# 28Pins_Project_V1I1.net
KiCad netlist of a schematic drawn in Altium Designer
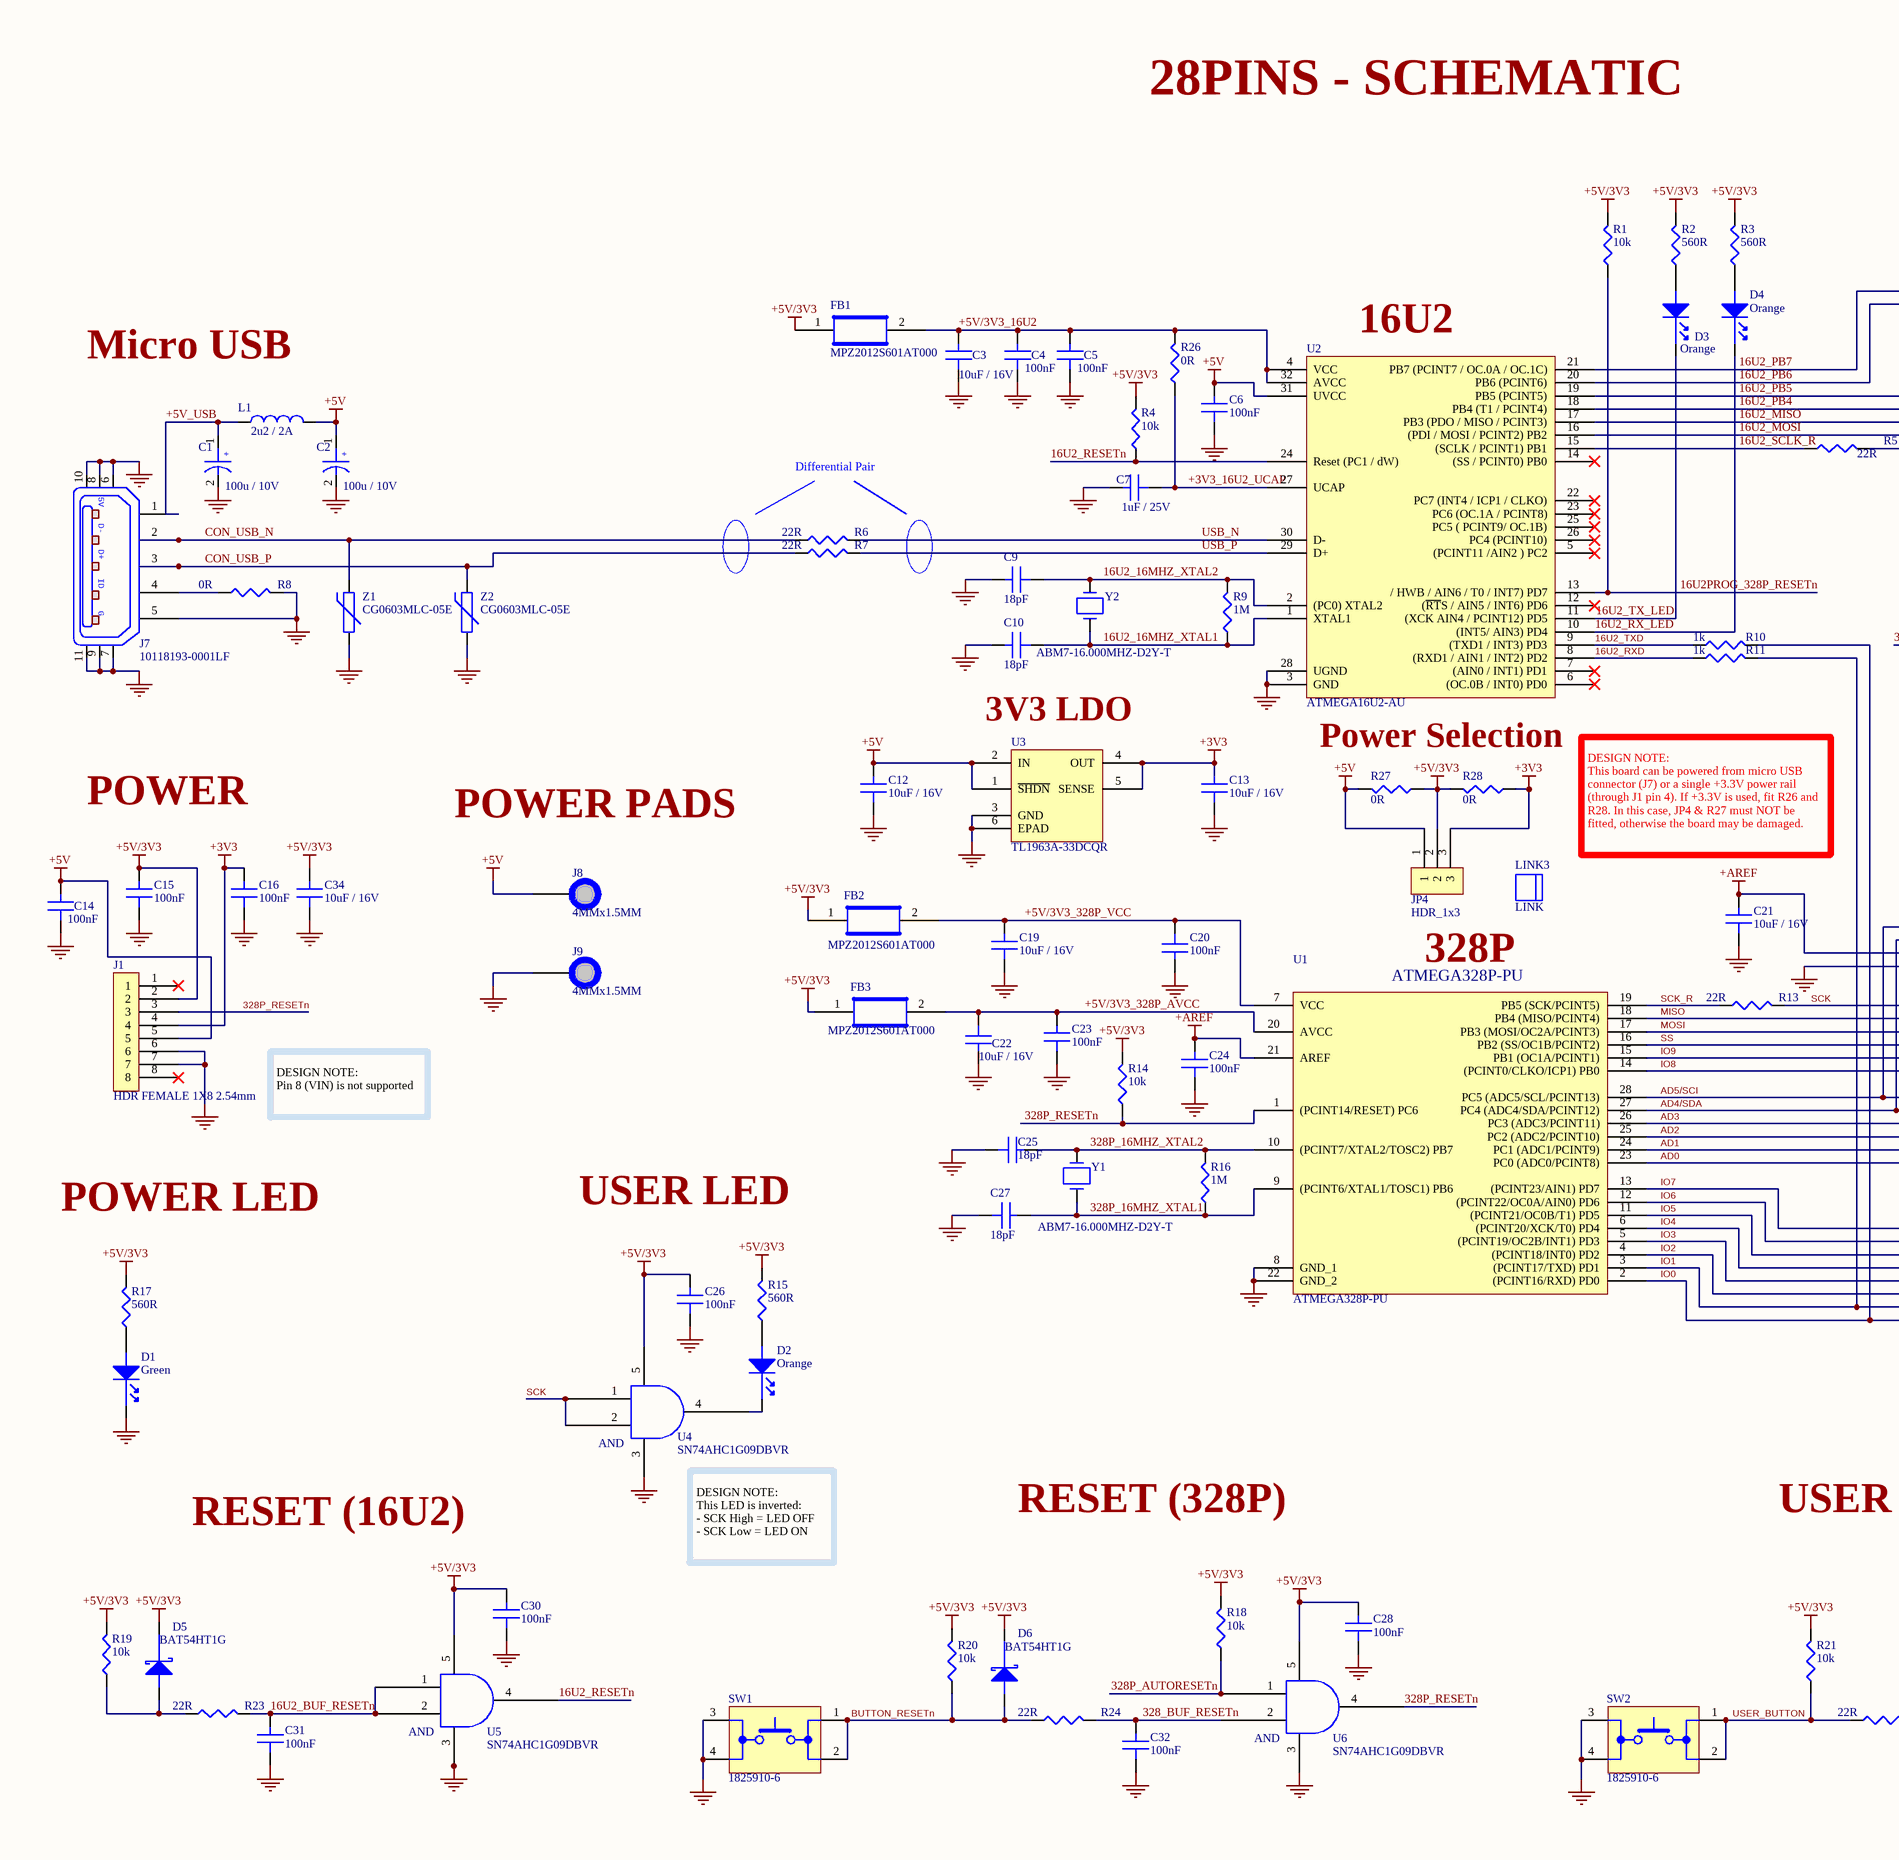
[diagram p0: 28Pins_Project_V1I1.SchDoc, left]
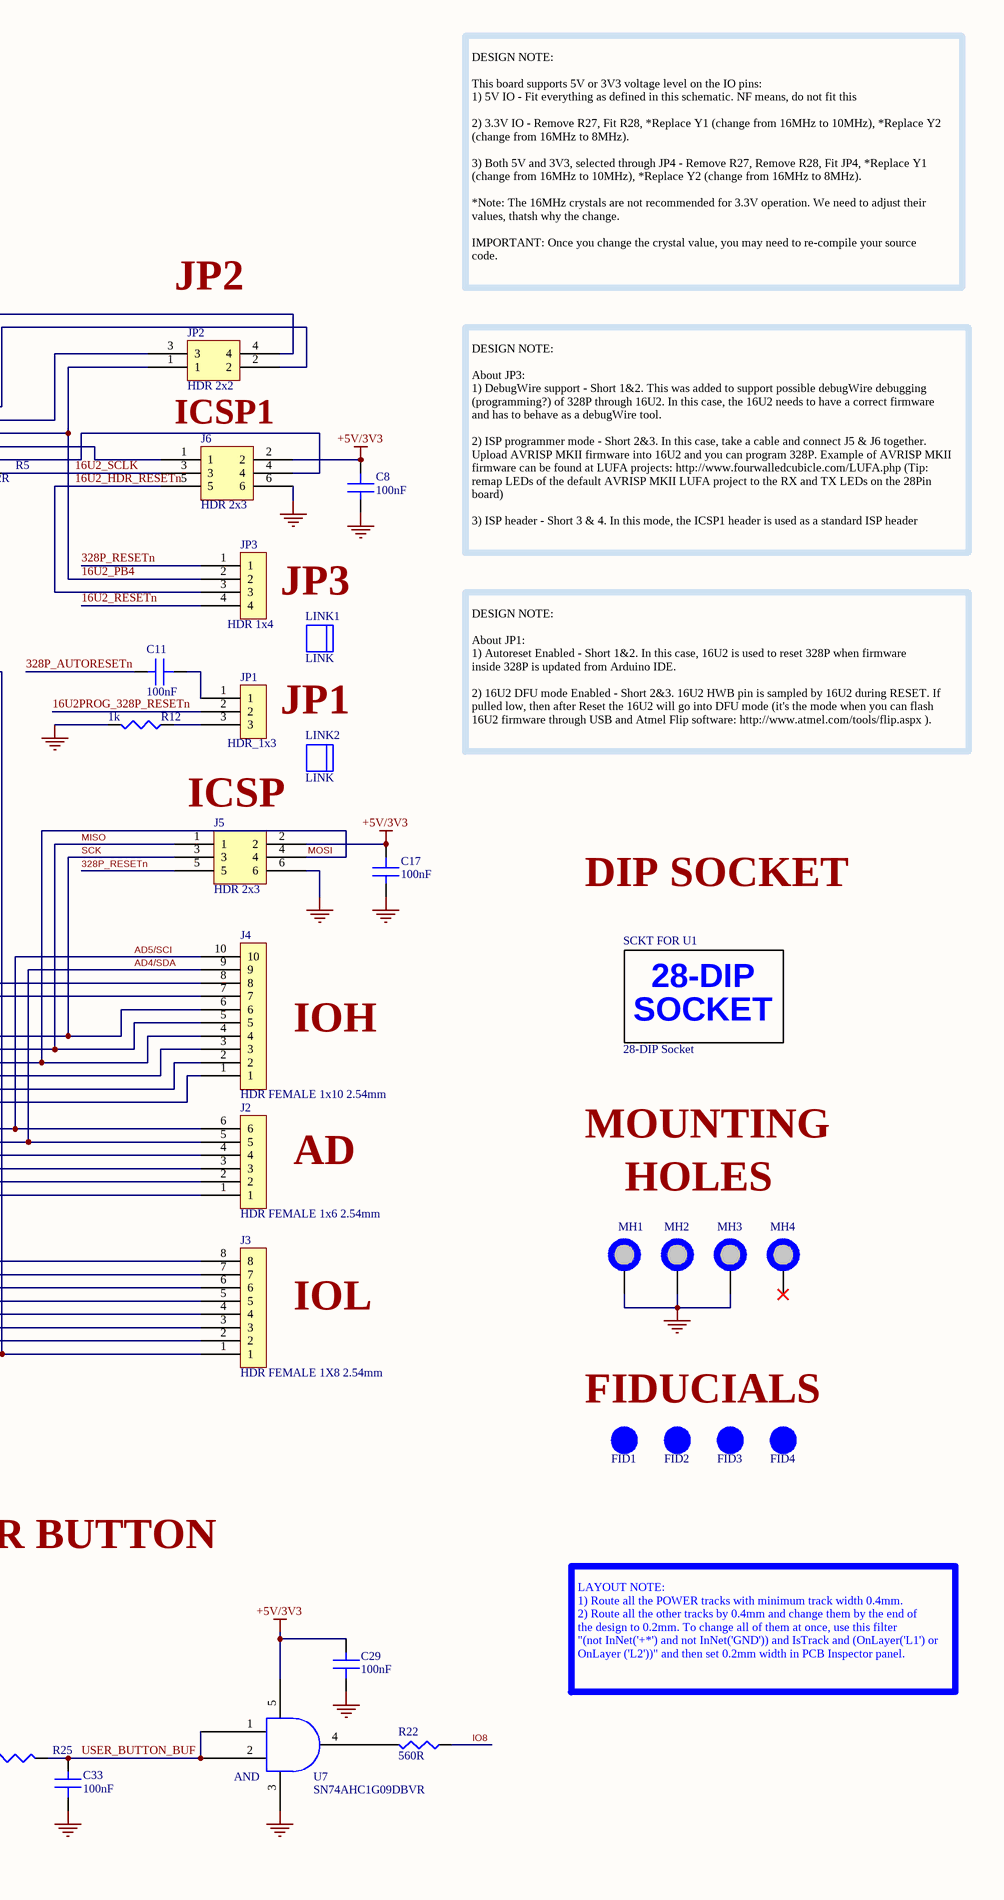
[diagram p1: 28Pins_Project_V1I1.SchDoc, right]

(export (version "E")
  (design (tool "Eeschema 10.0.6"))
  (components
    (comp (ref "C1")
      (value "100u / 10V")
      (footprint "C_ALU_C_SIZE")
      (description "CAP ALUM 100UF 20% 10V SMD")
      (fields
        (field (name "MANUFACTURER") "Panasonic")
        (field (name "MANUFACTURER PART NUMBER") "EEE-1AA101WR")
      )
      (libsource (lib "28Pins_Project_V1I1") (part "Tantal Capacitor"))
    )
    (comp (ref "C2")
      (value "100u / 10V")
      (footprint "C_ALU_C_SIZE")
      (description "CAP ALUM 100UF 20% 10V SMD")
      (fields
        (field (name "MANUFACTURER") "Panasonic")
        (field (name "MANUFACTURER PART NUMBER") "EEE-1AA101WR")
      )
      (libsource (lib "28Pins_Project_V1I1") (part "Tantal Capacitor"))
    )
    (comp (ref "C3")
      (value "10uF / 16V")
      (footprint "Capacitor 0805")
      (fields
        (field (name "MANUFACTURER") "TDK")
        (field (name "MANUFACTURER PART NUMBER") "C2012X5R1C106M125AC")
        (field (name "TOLERANCE") "20%")
      )
      (libsource (lib "28Pins_Project_V1I1") (part "C2012X5R1C106M125AC"))
    )
    (comp (ref "C4")
      (value "100nF")
      (footprint "Capacitor 0805")
      (description "100 nF Capacitor")
      (libsource (lib "28Pins_Project_V1I1") (part "CAP 0805 100nF"))
    )
    (comp (ref "C5")
      (value "100nF")
      (footprint "Capacitor 0805")
      (description "100 nF Capacitor")
      (libsource (lib "28Pins_Project_V1I1") (part "CAP 0805 100nF"))
    )
    (comp (ref "C6")
      (value "100nF")
      (footprint "Capacitor 0805")
      (description "100 nF Capacitor")
      (libsource (lib "28Pins_Project_V1I1") (part "CAP 0805 100nF"))
    )
    (comp (ref "C7")
      (value "1uF / 25V")
      (footprint "Capacitor 0805")
      (description "CAP CER 1UF 25V X5R 0805")
      (fields
        (field (name "MANUFACTURER") "TDK")
        (field (name "MANUFACTURER PART NUMBER") "C2012X5R1E105K125AA")
      )
      (libsource (lib "28Pins_Project_V1I1") (part "C2012X5R1E105K125AA"))
    )
    (comp (ref "C8")
      (value "100nF")
      (footprint "Capacitor 0805")
      (description "100 nF Capacitor")
      (libsource (lib "28Pins_Project_V1I1") (part "CAP 0805 100nF"))
    )
    (comp (ref "C9")
      (value "18pF")
      (footprint "Capacitor 0805")
      (description "Cap Ceramic 18pF 50V C0G 5% SMD 0805 125C Paper T/R")
      (fields
        (field (name "MANUFACTURER") "KEMET")
        (field (name "MANUFACTURER PART NUMBER") "C0805C180J5GACTU")
      )
      (libsource (lib "28Pins_Project_V1I1") (part "C0805C180J5GACTU"))
    )
    (comp (ref "C10")
      (value "18pF")
      (footprint "Capacitor 0805")
      (description "Cap Ceramic 18pF 50V C0G 5% SMD 0805 125C Paper T/R")
      (fields
        (field (name "MANUFACTURER") "KEMET")
        (field (name "MANUFACTURER PART NUMBER") "C0805C180J5GACTU")
      )
      (libsource (lib "28Pins_Project_V1I1") (part "C0805C180J5GACTU"))
    )
    (comp (ref "C11")
      (value "100nF")
      (footprint "Capacitor 0805")
      (description "100 nF Capacitor")
      (libsource (lib "28Pins_Project_V1I1") (part "CAP 0805 100nF"))
    )
    (comp (ref "C12")
      (value "10uF / 16V")
      (footprint "Capacitor 0805")
      (fields
        (field (name "MANUFACTURER") "TDK")
        (field (name "MANUFACTURER PART NUMBER") "C2012X5R1C106M125AC")
        (field (name "TOLERANCE") "20%")
      )
      (libsource (lib "28Pins_Project_V1I1") (part "C2012X5R1C106M125AC"))
    )
    (comp (ref "C13")
      (value "10uF / 16V")
      (footprint "Capacitor 0805")
      (fields
        (field (name "MANUFACTURER") "TDK")
        (field (name "MANUFACTURER PART NUMBER") "C2012X5R1C106M125AC")
        (field (name "TOLERANCE") "20%")
      )
      (libsource (lib "28Pins_Project_V1I1") (part "C2012X5R1C106M125AC"))
    )
    (comp (ref "C14")
      (value "100nF")
      (footprint "Capacitor 0805")
      (description "100 nF Capacitor")
      (libsource (lib "28Pins_Project_V1I1") (part "CAP 0805 100nF"))
    )
    (comp (ref "C15")
      (value "100nF")
      (footprint "Capacitor 0805")
      (description "100 nF Capacitor")
      (libsource (lib "28Pins_Project_V1I1") (part "CAP 0805 100nF"))
    )
    (comp (ref "C16")
      (value "100nF")
      (footprint "Capacitor 0805")
      (description "100 nF Capacitor")
      (libsource (lib "28Pins_Project_V1I1") (part "CAP 0805 100nF"))
    )
    (comp (ref "C17")
      (value "100nF")
      (footprint "Capacitor 0805")
      (description "100 nF Capacitor")
      (libsource (lib "28Pins_Project_V1I1") (part "CAP 0805 100nF"))
    )
    (comp (ref "C19")
      (value "10uF / 16V")
      (footprint "Capacitor 0805")
      (fields
        (field (name "MANUFACTURER") "TDK")
        (field (name "MANUFACTURER PART NUMBER") "C2012X5R1C106M125AC")
        (field (name "TOLERANCE") "20%")
      )
      (libsource (lib "28Pins_Project_V1I1") (part "C2012X5R1C106M125AC"))
    )
    (comp (ref "C20")
      (value "100nF")
      (footprint "Capacitor 0805")
      (description "100 nF Capacitor")
      (libsource (lib "28Pins_Project_V1I1") (part "CAP 0805 100nF"))
    )
    (comp (ref "C21")
      (value "10uF / 16V")
      (footprint "Capacitor 0805")
      (fields
        (field (name "MANUFACTURER") "TDK")
        (field (name "MANUFACTURER PART NUMBER") "C2012X5R1C106M125AC")
        (field (name "TOLERANCE") "20%")
      )
      (libsource (lib "28Pins_Project_V1I1") (part "C2012X5R1C106M125AC"))
    )
    (comp (ref "C22")
      (value "10uF / 16V")
      (footprint "Capacitor 0805")
      (fields
        (field (name "MANUFACTURER") "TDK")
        (field (name "MANUFACTURER PART NUMBER") "C2012X5R1C106M125AC")
        (field (name "TOLERANCE") "20%")
      )
      (libsource (lib "28Pins_Project_V1I1") (part "C2012X5R1C106M125AC"))
    )
    (comp (ref "C23")
      (value "100nF")
      (footprint "Capacitor 0805")
      (description "100 nF Capacitor")
      (libsource (lib "28Pins_Project_V1I1") (part "CAP 0805 100nF"))
    )
    (comp (ref "C24")
      (value "100nF")
      (footprint "Capacitor 0805")
      (description "100 nF Capacitor")
      (libsource (lib "28Pins_Project_V1I1") (part "CAP 0805 100nF"))
    )
    (comp (ref "C25")
      (value "18pF")
      (footprint "Capacitor 0805")
      (description "Cap Ceramic 18pF 50V C0G 5% SMD 0805 125C Paper T/R")
      (fields
        (field (name "MANUFACTURER") "KEMET")
        (field (name "MANUFACTURER PART NUMBER") "C0805C180J5GACTU")
      )
      (libsource (lib "28Pins_Project_V1I1") (part "C0805C180J5GACTU"))
    )
    (comp (ref "C26")
      (value "100nF")
      (footprint "Capacitor 0805")
      (description "100 nF Capacitor")
      (libsource (lib "28Pins_Project_V1I1") (part "CAP 0805 100nF"))
    )
    (comp (ref "C27")
      (value "18pF")
      (footprint "Capacitor 0805")
      (description "Cap Ceramic 18pF 50V C0G 5% SMD 0805 125C Paper T/R")
      (fields
        (field (name "MANUFACTURER") "KEMET")
        (field (name "MANUFACTURER PART NUMBER") "C0805C180J5GACTU")
      )
      (libsource (lib "28Pins_Project_V1I1") (part "C0805C180J5GACTU"))
    )
    (comp (ref "C28")
      (value "100nF")
      (footprint "Capacitor 0805")
      (description "100 nF Capacitor")
      (libsource (lib "28Pins_Project_V1I1") (part "CAP 0805 100nF"))
    )
    (comp (ref "C29")
      (value "100nF")
      (footprint "Capacitor 0805")
      (description "100 nF Capacitor")
      (libsource (lib "28Pins_Project_V1I1") (part "CAP 0805 100nF"))
    )
    (comp (ref "C30")
      (value "100nF")
      (footprint "Capacitor 0805")
      (description "100 nF Capacitor")
      (libsource (lib "28Pins_Project_V1I1") (part "CAP 0805 100nF"))
    )
    (comp (ref "C31")
      (value "100nF")
      (footprint "Capacitor 0805")
      (description "100 nF Capacitor")
      (libsource (lib "28Pins_Project_V1I1") (part "CAP 0805 100nF"))
    )
    (comp (ref "C32")
      (value "100nF")
      (footprint "Capacitor 0805")
      (description "100 nF Capacitor")
      (libsource (lib "28Pins_Project_V1I1") (part "CAP 0805 100nF"))
    )
    (comp (ref "C33")
      (value "100nF")
      (footprint "Capacitor 0805")
      (description "100 nF Capacitor")
      (libsource (lib "28Pins_Project_V1I1") (part "CAP 0805 100nF"))
    )
    (comp (ref "C34")
      (value "10uF / 16V")
      (footprint "Capacitor 0805")
      (fields
        (field (name "MANUFACTURER") "TDK")
        (field (name "MANUFACTURER PART NUMBER") "C2012X5R1C106M125AC")
        (field (name "TOLERANCE") "20%")
      )
      (libsource (lib "28Pins_Project_V1I1") (part "C2012X5R1C106M125AC"))
    )
    (comp (ref "D1")
      (value "Green")
      (footprint "LED_0603")
      (description "LED GREEN DIFFUSED 0603 SMD")
      (fields
        (field (name "MANUFACTURER") "Osram Opto")
        (field (name "MANUFACTURER PART NUMBER") "LGL29K-G2J1-24-Z")
      )
      (libsource (lib "28Pins_Project_V1I1") (part "LGL29K-G2J1-24-Z"))
    )
    (comp (ref "D2")
      (value "Orange")
      (footprint "LED_0603")
      (description "LED Orange Diffused 0603 SMD")
      (fields
        (field (name "MANUFACTURER") "Osram Opto")
        (field (name "MANUFACTURER PART NUMBER") "LOL29K-H2K1-24-Z")
      )
      (libsource (lib "28Pins_Project_V1I1") (part "LOL29K-H2K1-24-Z"))
    )
    (comp (ref "D3")
      (value "Orange")
      (footprint "LED_0603")
      (description "LED Orange Diffused 0603 SMD")
      (fields
        (field (name "MANUFACTURER") "Osram Opto")
        (field (name "MANUFACTURER PART NUMBER") "LOL29K-H2K1-24-Z")
      )
      (libsource (lib "28Pins_Project_V1I1") (part "LOL29K-H2K1-24-Z"))
    )
    (comp (ref "D4")
      (value "Orange")
      (footprint "LED_0603")
      (description "LED Orange Diffused 0603 SMD")
      (fields
        (field (name "MANUFACTURER") "Osram Opto")
        (field (name "MANUFACTURER PART NUMBER") "LOL29K-H2K1-24-Z")
      )
      (libsource (lib "28Pins_Project_V1I1") (part "LOL29K-H2K1-24-Z"))
    )
    (comp (ref "D5")
      (value "BAT54HT1G")
      (footprint "SOD323")
      (description "Diode Schottky 30V 200mA SOD323")
      (fields (field (name "MANUFACTURER") "ON Semiconductor / Fairchild"))
      (libsource (lib "28Pins_Project_V1I1") (part "BAT54HT1G"))
    )
    (comp (ref "D6")
      (value "BAT54HT1G")
      (footprint "SOD323")
      (description "Diode Schottky 30V 200mA SOD323")
      (fields (field (name "MANUFACTURER") "ON Semiconductor / Fairchild"))
      (libsource (lib "28Pins_Project_V1I1") (part "BAT54HT1G"))
    )
    (comp (ref "FB1")
      (value "MPZ2012S601AT000")
      (footprint "Capacitor 0805")
      (description "0805 600Ω ±25% DCR=0.1Ω 2A")
      (fields (field (name "MANUFACTURER") "TDK"))
      (libsource (lib "28Pins_Project_V1I1") (part "MPZ2012S601AT000"))
    )
    (comp (ref "FB2")
      (value "MPZ2012S601AT000")
      (footprint "Capacitor 0805")
      (description "0805 600Ω ±25% DCR=0.1Ω 2A")
      (fields (field (name "MANUFACTURER") "TDK"))
      (libsource (lib "28Pins_Project_V1I1") (part "MPZ2012S601AT000"))
    )
    (comp (ref "FB3")
      (value "MPZ2012S601AT000")
      (footprint "Capacitor 0805")
      (description "0805 600Ω ±25% DCR=0.1Ω 2A")
      (fields (field (name "MANUFACTURER") "TDK"))
      (libsource (lib "28Pins_Project_V1I1") (part "MPZ2012S601AT000"))
    )
    (comp (ref "FID1")
      (value "FID_1MMC")
      (footprint "FID_40X120D")
      (description "Fiducial 40mil Diameter, 120mil mask")
      (libsource (lib "28Pins_Project_V1I1") (part "FID_1MMC"))
    )
    (comp (ref "FID2")
      (value "FID_1MMC")
      (footprint "FID_40X120D")
      (description "Fiducial 40mil Diameter, 120mil mask")
      (libsource (lib "28Pins_Project_V1I1") (part "FID_1MMC"))
    )
    (comp (ref "FID3")
      (value "FID_1MMC")
      (footprint "FID_40X120D")
      (description "Fiducial 40mil Diameter, 120mil mask")
      (libsource (lib "28Pins_Project_V1I1") (part "FID_1MMC"))
    )
    (comp (ref "FID4")
      (value "FID_1MMC")
      (footprint "FID_40X120D")
      (description "Fiducial 40mil Diameter, 120mil mask")
      (libsource (lib "28Pins_Project_V1I1") (part "FID_1MMC"))
    )
    (comp (ref "J1")
      (value "HDR FEMALE 1X8 2.54mm")
      (footprint "HDR FEMALE 1x8 2.54mm")
      (description "2.54mm (0.1\") Pitch SIL Vertical PC Tail Socket Assembly, selective gold + tin, 8 contacts")
      (fields (field (name "MANUFACTURER") "Harwin") (field (name "MANUFACTURER PART NUMBER") "M20-7820842"))
      (libsource (lib "28Pins_Project_V1I1") (part "M20-7820842"))
    )
    (comp (ref "J2")
      (value "HDR FEMALE 1x6 2.54mm")
      (footprint "HDR FEMALE 1x6 2.54mm - duplicate - duplicate")
      (description "2.54mm (0.1\") Pitch SIL Vertical PC Tail Socket Assembly, tin, 6 contacts")
      (fields (field (name "MANUFACTURER") "Harwin") (field (name "MANUFACTURER PART NUMBER") "M20-7820646"))
      (libsource (lib "28Pins_Project_V1I1") (part "M20-7820646"))
    )
    (comp (ref "J3")
      (value "HDR FEMALE 1X8 2.54mm")
      (footprint "HDR FEMALE 1x8 2.54mm")
      (description "2.54mm (0.1\") Pitch SIL Vertical PC Tail Socket Assembly, selective gold + tin, 8 contacts")
      (fields (field (name "MANUFACTURER") "Harwin") (field (name "MANUFACTURER PART NUMBER") "M20-7820842"))
      (libsource (lib "") (part "M20-7820842_1"))
    )
    (comp (ref "J4")
      (value "HDR FEMALE 1x10 2.54mm")
      (footprint "Hdr_Female_1x10_2.54mm")
      (description "2.54mm (0.1\") Pitch SIL Vertical PC Tail Socket Assembly, tin, 10 contacts")
      (fields (field (name "MANUFACTURER") "Harwin") (field (name "MANUFACTURER PART NUMBER") "M20-7821046"))
      (libsource (lib "28Pins_Project_V1I1") (part "M20-7821046"))
    )
    (comp (ref "J5")
      (value "HDR 2x3")
      (footprint "HDR_2x3_2.54mm")
      (description "03+03 DIL Vert Pin Hdr")
      (fields (field (name "MANUFACTURER") "Harwin") (field (name "MANUFACTURER PART NUMBER") "M20-9720345"))
      (libsource (lib "28Pins_Project_V1I1") (part "M20-9720345"))
    )
    (comp (ref "J6")
      (value "HDR 2x3")
      (footprint "HDR_2x3_2.54mm")
      (description "03+03 DIL Vert Pin Hdr")
      (fields (field (name "MANUFACTURER") "Harwin") (field (name "MANUFACTURER PART NUMBER") "M20-9720345"))
      (libsource (lib "28Pins_Project_V1I1") (part "M20-9720345"))
    )
    (comp (ref "J7")
      (value "10118193-0001LF")
      (footprint "10118193")
      (description "CONN USB MICRO B RECPT SMT R/A")
      (fields (field (name "MANUFACTURER") "Amphenol ICC / FCI"))
      (libsource (lib "28Pins_Project_V1I1") (part "MICRO USB"))
    )
    (comp (ref "J8")
      (value "4MMx1.5MM")
      (footprint "PAD_WITH_HOLE_4MMx1.5MM")
      (description "Pad with a hole 4mm x 1.5mm")
      (libsource (lib "28Pins_Project_V1I1") (part "PAD_WITH_HOLE_4MMx1.5MM"))
    )
    (comp (ref "J9")
      (value "4MMx1.5MM")
      (footprint "PAD_WITH_HOLE_4MMx1.5MM")
      (description "Pad with a hole 4mm x 1.5mm")
      (libsource (lib "28Pins_Project_V1I1") (part "PAD_WITH_HOLE_4MMx1.5MM"))
    )
    (comp (ref "JP1")
      (value "HDR_1x3")
      (footprint "Hdr_1x3_2.54mm")
      (description "Conn Unshrouded Header HDR 3 POS 2.54mm Solder ST Top Entry Thru-Hole BergStik® Automotive Bulk")
      (fields
        (field (name "MANUFACTURER") "Amphenol ICC / FCI")
        (field (name "MANUFACTURER PART NUMBER") "68000-103HLF")
      )
      (libsource (lib "") (part "68000-103HLF_1"))
    )
    (comp (ref "JP2")
      (value "HDR 2x2")
      (footprint "HDR_2x2_2.54mm")
      (description "Conn Unshrouded Header HDR 4 POS 2.54mm Solder ST Top Entry Thru-Hole BergStik® Bulk")
      (fields
        (field (name "MANUFACTURER") "AMPHENOL ICC (FCI)")
        (field (name "MANUFACTURER PART NUMBER") "68602-204HLF")
      )
      (libsource (lib "28Pins_Project_V1I1") (part "Header - 68602-204HLF"))
    )
    (comp (ref "JP3")
      (value "HDR 1x4")
      (footprint "HDR_1x4 2.54mm")
      (description "HDR 4 POS 2.54mm Solder ST Thru-Hole Bag\r\nConn Unshrouded Header")
      (fields
        (field (name "MANUFACTURER") "Amphenol ICC")
        (field (name "MANUFACTURER PART NUMBER") "68001-204HLF")
      )
      (libsource (lib "28Pins_Project_V1I1") (part "68001-204HLF"))
    )
    (comp (ref "JP4")
      (value "HDR_1x3")
      (footprint "Hdr_1x3_2.54mm")
      (description "Conn Unshrouded Header HDR 3 POS 2.54mm Solder ST Top Entry Thru-Hole BergStik® Automotive Bulk")
      (fields
        (field (name "MANUFACTURER") "Amphenol ICC / FCI")
        (field (name "MANUFACTURER PART NUMBER") "68000-103HLF")
      )
      (libsource (lib "28Pins_Project_V1I1") (part "68000-103HLF"))
    )
    (comp (ref "L1")
      (value "2u2 / 2A")
      (footprint "C1210_IND")
      (description "FIXED IND 2.2UH 2A 80 MOHM SMD")
      (fields
        (field (name "MANUFACTURER") "KEMET")
        (field (name "MANUFACTURER PART NUMBER") "L1210R2R2MDWIT")
      )
      (libsource (lib "28Pins_Project_V1I1") (part "INDUCTOR"))
    )
    (comp (ref "LINK1")
      (value "LINK")
      (description "CONN JUMPER SHORTING .100* GOLD")
      (fields
        (field (name "MANUFACTURER") "Sullins")
        (field (name "MANUFACTURER PART NUMBER") "QPC02SXGN-RC")
      )
      (libsource (lib "28Pins_Project_V1I1") (part "LINK"))
    )
    (comp (ref "LINK2")
      (value "LINK")
      (description "CONN JUMPER SHORTING .100* GOLD")
      (fields
        (field (name "MANUFACTURER") "Sullins")
        (field (name "MANUFACTURER PART NUMBER") "QPC02SXGN-RC")
      )
      (libsource (lib "28Pins_Project_V1I1") (part "LINK"))
    )
    (comp (ref "LINK3")
      (value "LINK")
      (description "CONN JUMPER SHORTING .100* GOLD")
      (fields
        (field (name "MANUFACTURER") "Sullins")
        (field (name "MANUFACTURER PART NUMBER") "QPC02SXGN-RC")
      )
      (libsource (lib "28Pins_Project_V1I1") (part "LINK"))
    )
    (comp (ref "MH1")
      (value "MH_7.4MMC_3.2MMD")
      (footprint "MH_7.4MMC_3.2MMD")
      (description "Mounting Hole 7.4mm Diameter, 3.2mm Drill")
      (libsource (lib "28Pins_Project_V1I1") (part "MH_7.4MMC_3.2MMD"))
    )
    (comp (ref "MH2")
      (value "MH_7.4MMC_3.2MMD")
      (footprint "MH_7.4MMC_3.2MMD")
      (description "Mounting Hole 7.4mm Diameter, 3.2mm Drill")
      (libsource (lib "28Pins_Project_V1I1") (part "MH_7.4MMC_3.2MMD"))
    )
    (comp (ref "MH3")
      (value "MH_7.4MMC_3.2MMD")
      (footprint "MH_7.4MMC_3.2MMD")
      (description "Mounting Hole 7.4mm Diameter, 3.2mm Drill")
      (libsource (lib "28Pins_Project_V1I1") (part "MH_7.4MMC_3.2MMD"))
    )
    (comp (ref "MH4")
      (value "MH_7.4MMNC_3.2MMD")
      (footprint "MH_7.4MMD_3.2MMD_NON_COPPER_NPTH")
      (description "Hole 7.4mm Diameter (Non Copper,) 3.2mm Drill NPTH")
      (libsource (lib "28Pins_Project_V1I1") (part "MH_7.4MMNC_3.2MMD"))
    )
    (comp (ref "R1")
      (value "10k")
      (footprint "R0805")
      (description "Res Thick Film 0805 10K Ohm 1% 0.125W(1/8W) +/-100ppm/C Epoxy Pad SMD T/R")
      (fields
        (field (name "MANUFACTURER") "Yageo")
        (field (name "MANUFACTURER PART NUMBER") "RC0805FR-0710KL")
      )
      (libsource (lib "28Pins_Project_V1I1") (part "Res SMD 10K Ohm RC0805FR-0710KL"))
    )
    (comp (ref "R2")
      (value "560R")
      (footprint "R0805")
      (description "RES SMD 560 OHM 1% 1/8W 0805")
      (fields
        (field (name "MANUFACTURER") "Yageo")
        (field (name "MANUFACTURER PART NUMBER") "RC0805FR-07560RL")
      )
      (libsource (lib "28Pins_Project_V1I1") (part "RC0805FR-07560RL"))
    )
    (comp (ref "R3")
      (value "560R")
      (footprint "R0805")
      (description "RES SMD 560 OHM 1% 1/8W 0805")
      (fields
        (field (name "MANUFACTURER") "Yageo")
        (field (name "MANUFACTURER PART NUMBER") "RC0805FR-07560RL")
      )
      (libsource (lib "28Pins_Project_V1I1") (part "RC0805FR-07560RL"))
    )
    (comp (ref "R4")
      (value "10k")
      (footprint "R0805")
      (description "Res Thick Film 0805 10K Ohm 1% 0.125W(1/8W) +/-100ppm/C Epoxy Pad SMD T/R")
      (fields
        (field (name "MANUFACTURER") "Yageo")
        (field (name "MANUFACTURER PART NUMBER") "RC0805FR-0710KL")
      )
      (libsource (lib "28Pins_Project_V1I1") (part "Res SMD 10K Ohm RC0805FR-0710KL"))
    )
    (comp (ref "R5")
      (value "22R")
      (footprint "R0805")
      (description "Res Thick Film 0805 22 Ohm 1% 0.125W(1/8W) ±100ppm/C Pad SMD T/R")
      (fields
        (field (name "MANUFACTURER") "Yageo")
        (field (name "MANUFACTURER PART NUMBER") "RC0805FR-0722RL")
      )
      (libsource (lib "28Pins_Project_V1I1") (part "Res SMD 22 Ohm"))
    )
    (comp (ref "R6")
      (value "22R")
      (footprint "R0805")
      (description "Res Thick Film 0805 22 Ohm 1% 0.125W(1/8W) ±100ppm/C Pad SMD T/R")
      (fields
        (field (name "MANUFACTURER") "Yageo")
        (field (name "MANUFACTURER PART NUMBER") "RC0805FR-0722RL")
      )
      (libsource (lib "28Pins_Project_V1I1") (part "Res SMD 22 Ohm"))
    )
    (comp (ref "R7")
      (value "22R")
      (footprint "R0805")
      (description "Res Thick Film 0805 22 Ohm 1% 0.125W(1/8W) ±100ppm/C Pad SMD T/R")
      (fields
        (field (name "MANUFACTURER") "Yageo")
        (field (name "MANUFACTURER PART NUMBER") "RC0805FR-0722RL")
      )
      (libsource (lib "28Pins_Project_V1I1") (part "Res SMD 22 Ohm"))
    )
    (comp (ref "R8")
      (value "0R")
      (footprint "R0805")
      (description "RES SMD 0.0 OHM JUMPER 1/8W 0805")
      (fields
        (field (name "MANUFACTURER") "Yageo")
        (field (name "MANUFACTURER PART NUMBER") "RC0805JR-070RL")
      )
      (libsource (lib "28Pins_Project_V1I1") (part "RC0805JR-070RL"))
    )
    (comp (ref "R9")
      (value "1M")
      (footprint "R0805")
      (description "Res Thick Film 0805 1M Ohm 1% 0.125W(1/8W) ±100ppm/C Pad SMD T/R")
      (fields
        (field (name "MANUFACTURER") "Yageo")
        (field (name "MANUFACTURER PART NUMBER") "RC0805FR-071ML")
      )
      (libsource (lib "28Pins_Project_V1I1") (part "RC0805FR-071ML"))
    )
    (comp (ref "R10")
      (value "1k")
      (footprint "R0805")
      (description "RES SMD 1K OHM 1% 1/8W 0805")
      (fields
        (field (name "MANUFACTURER") "Yageo")
        (field (name "MANUFACTURER PART NUMBER") "RC0805FR-071KL")
      )
      (libsource (lib "28Pins_Project_V1I1") (part "Res SMD 1K Ohm"))
    )
    (comp (ref "R11")
      (value "1k")
      (footprint "R0805")
      (description "RES SMD 1K OHM 1% 1/8W 0805")
      (fields
        (field (name "MANUFACTURER") "Yageo")
        (field (name "MANUFACTURER PART NUMBER") "RC0805FR-071KL")
      )
      (libsource (lib "28Pins_Project_V1I1") (part "Res SMD 1K Ohm"))
    )
    (comp (ref "R12")
      (value "1k")
      (footprint "R0805")
      (description "RES SMD 1K OHM 1% 1/8W 0805")
      (fields
        (field (name "MANUFACTURER") "Yageo")
        (field (name "MANUFACTURER PART NUMBER") "RC0805FR-071KL")
      )
      (libsource (lib "28Pins_Project_V1I1") (part "Res SMD 1K Ohm"))
    )
    (comp (ref "R13")
      (value "22R")
      (footprint "R0805")
      (description "Res Thick Film 0805 22 Ohm 1% 0.125W(1/8W) ±100ppm/C Pad SMD T/R")
      (fields
        (field (name "MANUFACTURER") "Yageo")
        (field (name "MANUFACTURER PART NUMBER") "RC0805FR-0722RL")
      )
      (libsource (lib "28Pins_Project_V1I1") (part "Res SMD 22 Ohm"))
    )
    (comp (ref "R14")
      (value "10k")
      (footprint "R0805")
      (description "Res Thick Film 0805 10K Ohm 1% 0.125W(1/8W) +/-100ppm/C Epoxy Pad SMD T/R")
      (fields
        (field (name "MANUFACTURER") "Yageo")
        (field (name "MANUFACTURER PART NUMBER") "RC0805FR-0710KL")
      )
      (libsource (lib "28Pins_Project_V1I1") (part "Res SMD 10K Ohm RC0805FR-0710KL"))
    )
    (comp (ref "R15")
      (value "560R")
      (footprint "R0805")
      (description "RES SMD 560 OHM 1% 1/8W 0805")
      (fields
        (field (name "MANUFACTURER") "Yageo")
        (field (name "MANUFACTURER PART NUMBER") "RC0805FR-07560RL")
      )
      (libsource (lib "28Pins_Project_V1I1") (part "RC0805FR-07560RL"))
    )
    (comp (ref "R16")
      (value "1M")
      (footprint "R0805")
      (description "Res Thick Film 0805 1M Ohm 1% 0.125W(1/8W) ±100ppm/C Pad SMD T/R")
      (fields
        (field (name "MANUFACTURER") "Yageo")
        (field (name "MANUFACTURER PART NUMBER") "RC0805FR-071ML")
      )
      (libsource (lib "28Pins_Project_V1I1") (part "RC0805FR-071ML"))
    )
    (comp (ref "R17")
      (value "560R")
      (footprint "R0805")
      (description "RES SMD 560 OHM 1% 1/8W 0805")
      (fields
        (field (name "MANUFACTURER") "Yageo")
        (field (name "MANUFACTURER PART NUMBER") "RC0805FR-07560RL")
      )
      (libsource (lib "28Pins_Project_V1I1") (part "RC0805FR-07560RL"))
    )
    (comp (ref "R18")
      (value "10k")
      (footprint "R0805")
      (description "Res Thick Film 0805 10K Ohm 1% 0.125W(1/8W) +/-100ppm/C Epoxy Pad SMD T/R")
      (fields
        (field (name "MANUFACTURER") "Yageo")
        (field (name "MANUFACTURER PART NUMBER") "RC0805FR-0710KL")
      )
      (libsource (lib "28Pins_Project_V1I1") (part "Res SMD 10K Ohm RC0805FR-0710KL"))
    )
    (comp (ref "R19")
      (value "10k")
      (footprint "R0805")
      (description "Res Thick Film 0805 10K Ohm 1% 0.125W(1/8W) +/-100ppm/C Epoxy Pad SMD T/R")
      (fields
        (field (name "MANUFACTURER") "Yageo")
        (field (name "MANUFACTURER PART NUMBER") "RC0805FR-0710KL")
      )
      (libsource (lib "28Pins_Project_V1I1") (part "Res SMD 10K Ohm RC0805FR-0710KL"))
    )
    (comp (ref "R20")
      (value "10k")
      (footprint "R0805")
      (description "Res Thick Film 0805 10K Ohm 1% 0.125W(1/8W) +/-100ppm/C Epoxy Pad SMD T/R")
      (fields
        (field (name "MANUFACTURER") "Yageo")
        (field (name "MANUFACTURER PART NUMBER") "RC0805FR-0710KL")
      )
      (libsource (lib "28Pins_Project_V1I1") (part "Res SMD 10K Ohm RC0805FR-0710KL"))
    )
    (comp (ref "R21")
      (value "10k")
      (footprint "R0805")
      (description "Res Thick Film 0805 10K Ohm 1% 0.125W(1/8W) +/-100ppm/C Epoxy Pad SMD T/R")
      (fields
        (field (name "MANUFACTURER") "Yageo")
        (field (name "MANUFACTURER PART NUMBER") "RC0805FR-0710KL")
      )
      (libsource (lib "28Pins_Project_V1I1") (part "Res SMD 10K Ohm RC0805FR-0710KL"))
    )
    (comp (ref "R22")
      (value "560R")
      (footprint "R0805")
      (description "RES SMD 560 OHM 1% 1/8W 0805")
      (fields
        (field (name "MANUFACTURER") "Yageo")
        (field (name "MANUFACTURER PART NUMBER") "RC0805FR-07560RL")
      )
      (libsource (lib "28Pins_Project_V1I1") (part "RC0805FR-07560RL"))
    )
    (comp (ref "R23")
      (value "22R")
      (footprint "R0805")
      (description "Res Thick Film 0805 22 Ohm 1% 0.125W(1/8W) ±100ppm/C Pad SMD T/R")
      (fields
        (field (name "MANUFACTURER") "Yageo")
        (field (name "MANUFACTURER PART NUMBER") "RC0805FR-0722RL")
      )
      (libsource (lib "28Pins_Project_V1I1") (part "Res SMD 22 Ohm"))
    )
    (comp (ref "R24")
      (value "22R")
      (footprint "R0805")
      (description "Res Thick Film 0805 22 Ohm 1% 0.125W(1/8W) ±100ppm/C Pad SMD T/R")
      (fields
        (field (name "MANUFACTURER") "Yageo")
        (field (name "MANUFACTURER PART NUMBER") "RC0805FR-0722RL")
      )
      (libsource (lib "28Pins_Project_V1I1") (part "Res SMD 22 Ohm"))
    )
    (comp (ref "R25")
      (value "22R")
      (footprint "R0805")
      (description "Res Thick Film 0805 22 Ohm 1% 0.125W(1/8W) ±100ppm/C Pad SMD T/R")
      (fields
        (field (name "MANUFACTURER") "Yageo")
        (field (name "MANUFACTURER PART NUMBER") "RC0805FR-0722RL")
      )
      (libsource (lib "28Pins_Project_V1I1") (part "Res SMD 22 Ohm"))
    )
    (comp (ref "R26")
      (value "0R")
      (footprint "R0805")
      (description "RES SMD 0.0 OHM JUMPER 1/8W 0805")
      (fields
        (field (name "MANUFACTURER") "Yageo")
        (field (name "MANUFACTURER PART NUMBER") "RC0805JR-070RL")
      )
      (libsource (lib "28Pins_Project_V1I1") (part "RC0805JR-070RL"))
    )
    (comp (ref "R27")
      (value "0R")
      (footprint "R0805")
      (description "RES SMD 0.0 OHM JUMPER 1/8W 0805")
      (fields
        (field (name "MANUFACTURER") "Yageo")
        (field (name "MANUFACTURER PART NUMBER") "RC0805JR-070RL")
      )
      (libsource (lib "28Pins_Project_V1I1") (part "RC0805JR-070RL"))
    )
    (comp (ref "R28")
      (value "0R")
      (footprint "R0805")
      (description "RES SMD 0.0 OHM JUMPER 1/8W 0805")
      (fields
        (field (name "MANUFACTURER") "Yageo")
        (field (name "MANUFACTURER PART NUMBER") "RC0805JR-070RL")
      )
      (libsource (lib "28Pins_Project_V1I1") (part "RC0805JR-070RL"))
    )
    (comp (ref "SCKT FOR U1")
      (value "28-DIP Socket")
      (footprint "28_DIP_7.62mm_SOCKET")
      (description "CONN IC DIP SOCKET 28POS TIN")
      (fields (field (name "MANUFACTURER") "3M") (field (name "MANUFACTURER PART NUMBER") "4828-3004-CP"))
      (libsource (lib "28Pins_Project_V1I1") (part "4828-3004-CP"))
    )
    (comp (ref "SW1")
      (value "1825910-6")
      (footprint "1825910-6")
      (description "Switch Tactile SPST -NO 0.05A 24V")
      (fields (field (name "MANUFACTURER") "TE Connectivity Alcoswitch"))
      (libsource (lib "28Pins_Project_V1I1") (part "Button"))
    )
    (comp (ref "SW2")
      (value "1825910-6")
      (footprint "1825910-6")
      (description "Switch Tactile SPST -NO 0.05A 24V")
      (fields (field (name "MANUFACTURER") "TE Connectivity Alcoswitch"))
      (libsource (lib "28Pins_Project_V1I1") (part "Button"))
    )
    (comp (ref "U1")
      (value "ATMEGA328P-PU")
      (footprint "DIP28")
      (description "ATMEGA328P-PU; 8 bit Microcontroller AVR 20MHz 1; 32kb Flash; 2kb RAM; I2C SPI 2")
      (fields (field (name "MANUFACTURER") "Microchip / Atmel"))
      (libsource (lib "28Pins_Project_V1I1") (part "ATMEGA328P-PU"))
    )
    (comp (ref "U2")
      (value "ATMEGA16U2-AU")
      (footprint "TQFP32")
      (description "8-bit AVR MCU, 16 KB, 512 Bytes, 16 MHz, 2.7 to 5.5V, TQFP-32, RoHS")
      (fields (field (name "MANUFACTURER") "Microchip / Atmel"))
      (libsource (lib "28Pins_Project_V1I1") (part "ATMEGA16U2-AU"))
    )
    (comp (ref "U3")
      (value "TL1963A-33DCQR")
      (footprint "DCQ (R-PDSO-G6)")
      (description "IC REG LDO 3.3V 1.5A SOT223-6")
      (fields (field (name "MANUFACTURER") "Texas Instruments"))
      (libsource (lib "28Pins_Project_V1I1") (part "3.3V REG"))
    )
    (comp (ref "U4")
      (value "SN74AHC1G09DBVR")
      (footprint "DBV_SOT_23_5")
      (description "IC GATE AND 1CH 2-INP SOT-23-5")
      (fields (field (name "MANUFACTURER") "Texas Instruments"))
      (libsource (lib "28Pins_Project_V1I1") (part "AND Gate"))
    )
    (comp (ref "U5")
      (value "SN74AHC1G09DBVR")
      (footprint "DBV_SOT_23_5")
      (description "IC GATE AND 1CH 2-INP SOT-23-5")
      (fields (field (name "MANUFACTURER") "Texas Instruments"))
      (libsource (lib "28Pins_Project_V1I1") (part "AND Gate"))
    )
    (comp (ref "U6")
      (value "SN74AHC1G09DBVR")
      (footprint "DBV_SOT_23_5")
      (description "IC GATE AND 1CH 2-INP SOT-23-5")
      (fields (field (name "MANUFACTURER") "Texas Instruments"))
      (libsource (lib "28Pins_Project_V1I1") (part "AND Gate"))
    )
    (comp (ref "U7")
      (value "SN74AHC1G09DBVR")
      (footprint "DBV_SOT_23_5")
      (description "IC GATE AND 1CH 2-INP SOT-23-5")
      (fields (field (name "MANUFACTURER") "Texas Instruments"))
      (libsource (lib "28Pins_Project_V1I1") (part "AND Gate"))
    )
    (comp (ref "Y1")
      (value "ABM7-16.000MHZ-D2Y-T")
      (footprint "APM7_v1_1_BIG")
      (description "Crystal 16MHz ±20ppm (Tol) ±30ppm (Stability) 18pF FUND 50Ohm 2-Pin Mini-CSMD T/R")
      (fields (field (name "MANUFACTURER") "Abracon") (field (name "TOLERANCE") "20ppm"))
      (libsource (lib "28Pins_Project_V1I1") (part "ABM7-16.000MHZ-D2Y-T"))
    )
    (comp (ref "Y2")
      (value "ABM7-16.000MHZ-D2Y-T")
      (footprint "APM7_v1_1_BIG")
      (description "Crystal 16MHz ±20ppm (Tol) ±30ppm (Stability) 18pF FUND 50Ohm 2-Pin Mini-CSMD T/R")
      (fields (field (name "MANUFACTURER") "Abracon") (field (name "TOLERANCE") "20ppm"))
      (libsource (lib "28Pins_Project_V1I1") (part "ABM7-16.000MHZ-D2Y-T"))
    )
    (comp (ref "Z1")
      (value "CG0603MLC-05E")
      (footprint "R0603")
      (description "VARISTOR 0603")
      (fields (field (name "MANUFACTURER") "Bourns") (field (name "VOLTAGE") "5V"))
      (libsource (lib "28Pins_Project_V1I1") (part "CG0603MLC-05E"))
    )
    (comp (ref "Z2")
      (value "CG0603MLC-05E")
      (footprint "R0603")
      (description "VARISTOR 0603")
      (fields (field (name "MANUFACTURER") "Bourns") (field (name "VOLTAGE") "5V"))
      (libsource (lib "28Pins_Project_V1I1") (part "CG0603MLC-05E"))
    )
  )
  (nets
    (net (code "1") (name "+3V3") (class "Default")
      (node (ref "C13") (pin "1") (pinfunction "1_1") (pintype "passive"))
      (node (ref "C16") (pin "1") (pinfunction "1_1") (pintype "passive"))
      (node (ref "J1") (pin "4") (pinfunction "4_4") (pintype "passive"))
      (node (ref "JP4") (pin "3") (pinfunction "3_3") (pintype "passive"))
      (node (ref "R28") (pin "1") (pinfunction "1_1") (pintype "passive"))
      (node (ref "U3") (pin "4") (pinfunction "OUT_4") (pintype "passive"))
      (node (ref "U3") (pin "5") (pinfunction "SENSE_5") (pintype "passive"))
    )
    (net (code "2") (name "+5V") (class "Default")
      (node (ref "C12") (pin "1") (pinfunction "1_1") (pintype "passive"))
      (node (ref "C14") (pin "1") (pinfunction "1_1") (pintype "passive"))
      (node (ref "C2") (pin "1") (pinfunction "1_1") (pintype "passive"))
      (node (ref "C6") (pin "1") (pinfunction "1_1") (pintype "passive"))
      (node (ref "J1") (pin "5") (pinfunction "5_5") (pintype "passive"))
      (node (ref "J8") (pin "1") (pinfunction "1_1") (pintype "passive"))
      (node (ref "JP4") (pin "1") (pinfunction "1_1") (pintype "passive"))
      (node (ref "L1") (pin "2") (pinfunction "2_2") (pintype "passive"))
      (node (ref "R27") (pin "2") (pinfunction "2_2") (pintype "passive"))
      (node (ref "U2") (pin "31") (pinfunction "UVCC_31") (pintype "passive"))
      (node (ref "U3") (pin "1") (pinfunction "~{SHDN}_1") (pintype "passive"))
      (node (ref "U3") (pin "2") (pinfunction "IN_2") (pintype "passive"))
    )
    (net (code "3") (name "+5V{slash}3V3") (class "Default")
      (node (ref "C15") (pin "1") (pinfunction "1_1") (pintype "passive"))
      (node (ref "C17") (pin "2") (pinfunction "2_2") (pintype "passive"))
      (node (ref "C26") (pin "1") (pinfunction "1_1") (pintype "passive"))
      (node (ref "C28") (pin "1") (pinfunction "1_1") (pintype "passive"))
      (node (ref "C29") (pin "1") (pinfunction "1_1") (pintype "passive"))
      (node (ref "C30") (pin "1") (pinfunction "1_1") (pintype "passive"))
      (node (ref "C34") (pin "1") (pinfunction "1_1") (pintype "passive"))
      (node (ref "C8") (pin "2") (pinfunction "2_2") (pintype "passive"))
      (node (ref "D5") (pin "1") (pinfunction "Cathode_1") (pintype "passive"))
      (node (ref "D6") (pin "1") (pinfunction "Cathode_1") (pintype "passive"))
      (node (ref "FB1") (pin "1") (pinfunction "1_1") (pintype "passive"))
      (node (ref "FB2") (pin "1") (pinfunction "1_1") (pintype "passive"))
      (node (ref "FB3") (pin "1") (pinfunction "1_1") (pintype "passive"))
      (node (ref "J1") (pin "2") (pinfunction "2_2") (pintype "passive"))
      (node (ref "J5") (pin "2") (pinfunction "2_2") (pintype "passive"))
      (node (ref "J6") (pin "2") (pinfunction "2_2") (pintype "passive"))
      (node (ref "JP4") (pin "2") (pinfunction "2_2") (pintype "passive"))
      (node (ref "R1") (pin "2") (pinfunction "2_2") (pintype "passive"))
      (node (ref "R14") (pin "2") (pinfunction "2_2") (pintype "passive"))
      (node (ref "R15") (pin "2") (pinfunction "2_2") (pintype "passive"))
      (node (ref "R17") (pin "2") (pinfunction "2_2") (pintype "passive"))
      (node (ref "R18") (pin "2") (pinfunction "2_2") (pintype "passive"))
      (node (ref "R19") (pin "2") (pinfunction "2_2") (pintype "passive"))
      (node (ref "R2") (pin "2") (pinfunction "2_2") (pintype "passive"))
      (node (ref "R20") (pin "2") (pinfunction "2_2") (pintype "passive"))
      (node (ref "R21") (pin "2") (pinfunction "2_2") (pintype "passive"))
      (node (ref "R27") (pin "1") (pinfunction "1_1") (pintype "passive"))
      (node (ref "R28") (pin "2") (pinfunction "2_2") (pintype "passive"))
      (node (ref "R3") (pin "2") (pinfunction "2_2") (pintype "passive"))
      (node (ref "R4") (pin "2") (pinfunction "2_2") (pintype "passive"))
      (node (ref "U4") (pin "5") (pinfunction "5_5") (pintype "passive"))
      (node (ref "U5") (pin "5") (pinfunction "5_5") (pintype "passive"))
      (node (ref "U6") (pin "5") (pinfunction "5_5") (pintype "passive"))
      (node (ref "U7") (pin "5") (pinfunction "5_5") (pintype "passive"))
    )
    (net (code "4") (name "+AREF") (class "Default")
      (node (ref "C21") (pin "1") (pinfunction "1_1") (pintype "passive"))
      (node (ref "C24") (pin "1") (pinfunction "1_1") (pintype "passive"))
      (node (ref "J4") (pin "8") (pinfunction "8_8") (pintype "passive"))
      (node (ref "U1") (pin "21") (pinfunction "AREF_21") (pintype "passive"))
    )
    (net (code "5") (name "/+3V3_16U2_UCAP") (class "Default")
      (node (ref "C7") (pin "2") (pinfunction "2_2") (pintype "passive"))
      (node (ref "R26") (pin "1") (pinfunction "1_1") (pintype "passive"))
      (node (ref "U2") (pin "27") (pinfunction "UCAP_27") (pintype "passive"))
    )
    (net (code "6") (name "/+5V_USB") (class "Default")
      (node (ref "C1") (pin "1") (pinfunction "1_1") (pintype "passive"))
      (node (ref "J7") (pin "1") (pinfunction "1_1") (pintype "passive"))
      (node (ref "L1") (pin "1") (pinfunction "1_1") (pintype "passive"))
    )
    (net (code "7") (name "/+5V{slash}3V3_16U2") (class "Default")
      (node (ref "C3") (pin "1") (pinfunction "1_1") (pintype "passive"))
      (node (ref "C4") (pin "1") (pinfunction "1_1") (pintype "passive"))
      (node (ref "C5") (pin "1") (pinfunction "1_1") (pintype "passive"))
      (node (ref "FB1") (pin "2") (pinfunction "2_2") (pintype "passive"))
      (node (ref "R26") (pin "2") (pinfunction "2_2") (pintype "passive"))
      (node (ref "U2") (pin "32") (pinfunction "AVCC_32") (pintype "passive"))
      (node (ref "U2") (pin "4") (pinfunction "VCC_4") (pintype "passive"))
    )
    (net (code "8") (name "/+5V{slash}3V3_328P_AVCC") (class "Default")
      (node (ref "C22") (pin "2") (pinfunction "2_2") (pintype "passive"))
      (node (ref "C23") (pin "1") (pinfunction "1_1") (pintype "passive"))
      (node (ref "FB3") (pin "2") (pinfunction "2_2") (pintype "passive"))
      (node (ref "U1") (pin "20") (pinfunction "AVCC_20") (pintype "passive"))
    )
    (net (code "9") (name "/+5V{slash}3V3_328P_VCC") (class "Default")
      (node (ref "C19") (pin "1") (pinfunction "1_1") (pintype "passive"))
      (node (ref "C20") (pin "2") (pinfunction "2_2") (pintype "passive"))
      (node (ref "FB2") (pin "2") (pinfunction "2_2") (pintype "passive"))
      (node (ref "U1") (pin "7") (pinfunction "VCC_7") (pintype "passive"))
    )
    (net (code "10") (name "/16U2PROG_328P_RESETn") (class "Default")
      (node (ref "JP1") (pin "2") (pinfunction "2_2") (pintype "passive"))
      (node (ref "R1") (pin "1") (pinfunction "1_1") (pintype "passive"))
      (node (ref "U2") (pin "13") (pinfunction "/_HWB_/_AIN6_/_T0_/_INT7)_PD7_13") (pintype "passive"))
    )
    (net (code "11") (name "/16U2_16MHZ_XTAL1") (class "Default")
      (node (ref "C10") (pin "2") (pinfunction "2_2") (pintype "passive"))
      (node (ref "R9") (pin "1") (pinfunction "1_1") (pintype "passive"))
      (node (ref "U2") (pin "1") (pinfunction "XTAL1_1") (pintype "passive"))
      (node (ref "Y2") (pin "1") (pinfunction "1_1") (pintype "passive"))
    )
    (net (code "12") (name "/16U2_16MHZ_XTAL2") (class "Default")
      (node (ref "C9") (pin "2") (pinfunction "2_2") (pintype "passive"))
      (node (ref "R9") (pin "2") (pinfunction "2_2") (pintype "passive"))
      (node (ref "U2") (pin "2") (pinfunction "(PC0)_XTAL2_2") (pintype "passive"))
      (node (ref "Y2") (pin "2") (pinfunction "2_2") (pintype "passive"))
    )
    (net (code "13") (name "/16U2_BUF_RESETn") (class "Default")
      (node (ref "C31") (pin "1") (pinfunction "1_1") (pintype "passive"))
      (node (ref "R23") (pin "2") (pinfunction "2_2") (pintype "passive"))
      (node (ref "U5") (pin "1") (pinfunction "1_1") (pintype "passive"))
      (node (ref "U5") (pin "2") (pinfunction "2_2") (pintype "passive"))
    )
    (net (code "14") (name "/16U2_HDR_RESETn") (class "Default")
      (node (ref "J6") (pin "5") (pinfunction "5_5") (pintype "passive"))
      (node (ref "JP3") (pin "3") (pinfunction "3_3") (pintype "passive"))
    )
    (net (code "15") (name "/16U2_MISO") (class "Default")
      (node (ref "J6") (pin "1") (pinfunction "1_1") (pintype "passive"))
      (node (ref "U2") (pin "17") (pinfunction "PB3_(PDO_/_MISO_/_PCINT3)_17") (pintype "passive"))
    )
    (net (code "16") (name "/16U2_MOSI") (class "Default")
      (node (ref "J6") (pin "4") (pinfunction "4_4") (pintype "passive"))
      (node (ref "U2") (pin "16") (pinfunction "(PDI_/_MOSI_/_PCINT2)_PB2_16") (pintype "passive"))
    )
    (net (code "17") (name "/16U2_PB4") (class "Default")
      (node (ref "JP2") (pin "1") (pinfunction "1_1") (pintype "passive"))
      (node (ref "JP3") (pin "2") (pinfunction "2_2") (pintype "passive"))
      (node (ref "U2") (pin "18") (pinfunction "PB4_(T1_/_PCINT4)_18") (pintype "passive"))
    )
    (net (code "18") (name "/16U2_PB5") (class "Default")
      (node (ref "JP2") (pin "3") (pinfunction "3_3") (pintype "passive"))
      (node (ref "U2") (pin "19") (pinfunction "PB5_(PCINT5)_19") (pintype "passive"))
    )
    (net (code "19") (name "/16U2_PB6") (class "Default")
      (node (ref "JP2") (pin "2") (pinfunction "2_2") (pintype "passive"))
      (node (ref "U2") (pin "20") (pinfunction "PB6_(PCINT6)_20") (pintype "passive"))
    )
    (net (code "20") (name "/16U2_PB7") (class "Default")
      (node (ref "JP2") (pin "4") (pinfunction "4_4") (pintype "passive"))
      (node (ref "U2") (pin "21") (pinfunction "PB7_(PCINT7_/_OC.0A_/_OC.1C)_21") (pintype "passive"))
    )
    (net (code "21") (name "/16U2_RESETn") (class "Default")
      (node (ref "JP3") (pin "4") (pinfunction "4_4") (pintype "passive"))
      (node (ref "R4") (pin "1") (pinfunction "1_1") (pintype "passive"))
      (node (ref "U2") (pin "24") (pinfunction "Reset_(PC1_/_dW)_24") (pintype "passive"))
      (node (ref "U5") (pin "4") (pinfunction "4_4") (pintype "passive"))
    )
    (net (code "22") (name "/16U2_RXD") (class "Default")
      (node (ref "R11") (pin "1") (pinfunction "1_1") (pintype "passive"))
      (node (ref "U2") (pin "8") (pinfunction "(RXD1_/_AIN1_/_INT2)_PD2_8") (pintype "passive"))
    )
    (net (code "23") (name "/16U2_RX_LED") (class "Default")
      (node (ref "D4") (pin "1") (pinfunction "Cathode_1") (pintype "passive"))
      (node (ref "U2") (pin "10") (pinfunction "(INT5/_AIN3)_PD4_10") (pintype "passive"))
    )
    (net (code "24") (name "/16U2_SCLK") (class "Default")
      (node (ref "J6") (pin "3") (pinfunction "3_3") (pintype "passive"))
      (node (ref "R5") (pin "2") (pinfunction "2_2") (pintype "passive"))
    )
    (net (code "25") (name "/16U2_SCLK_R") (class "Default")
      (node (ref "R5") (pin "1") (pinfunction "1_1") (pintype "passive"))
      (node (ref "U2") (pin "15") (pinfunction "(SCLK_/_PCINT1)_PB1_15") (pintype "passive"))
    )
    (net (code "26") (name "/16U2_TXD") (class "Default")
      (node (ref "R10") (pin "1") (pinfunction "1_1") (pintype "passive"))
      (node (ref "U2") (pin "9") (pinfunction "(TXD1_/_INT3)_PD3_9") (pintype "passive"))
    )
    (net (code "27") (name "/16U2_TX_LED") (class "Default")
      (node (ref "D3") (pin "1") (pinfunction "Cathode_1") (pintype "passive"))
      (node (ref "U2") (pin "11") (pinfunction "(XCK_AIN4_/_PCINT12)_PD5_11") (pintype "passive"))
    )
    (net (code "28") (name "/328P_16MHZ_XTAL1") (class "Default")
      (node (ref "C27") (pin "1") (pinfunction "1_1") (pintype "passive"))
      (node (ref "R16") (pin "1") (pinfunction "1_1") (pintype "passive"))
      (node (ref "U1") (pin "9") (pinfunction "(PCINT6/XTAL1/TOSC1)_PB6_9") (pintype "passive"))
      (node (ref "Y1") (pin "1") (pinfunction "1_1") (pintype "passive"))
    )
    (net (code "29") (name "/328P_16MHZ_XTAL2") (class "Default")
      (node (ref "C25") (pin "1") (pinfunction "1_1") (pintype "passive"))
      (node (ref "R16") (pin "2") (pinfunction "2_2") (pintype "passive"))
      (node (ref "U1") (pin "10") (pinfunction "(PCINT7/XTAL2/TOSC2)_PB7_10") (pintype "passive"))
      (node (ref "Y1") (pin "2") (pinfunction "2_2") (pintype "passive"))
    )
    (net (code "30") (name "/328P_AUTORESETn") (class "Default")
      (node (ref "C11") (pin "1") (pinfunction "1_1") (pintype "passive"))
      (node (ref "R18") (pin "1") (pinfunction "1_1") (pintype "passive"))
      (node (ref "U6") (pin "1") (pinfunction "1_1") (pintype "passive"))
    )
    (net (code "31") (name "/328P_RESETn") (class "Default")
      (node (ref "J1") (pin "3") (pinfunction "3_3") (pintype "passive"))
      (node (ref "J5") (pin "5") (pinfunction "5_5") (pintype "passive"))
      (node (ref "JP3") (pin "1") (pinfunction "1_1") (pintype "passive"))
      (node (ref "R14") (pin "1") (pinfunction "1_1") (pintype "passive"))
      (node (ref "U1") (pin "1") (pinfunction "(PCINT14/RESET)_PC6_1") (pintype "passive"))
      (node (ref "U6") (pin "4") (pinfunction "4_4") (pintype "passive"))
    )
    (net (code "32") (name "/328_BUF_RESETn") (class "Default")
      (node (ref "C32") (pin "1") (pinfunction "1_1") (pintype "passive"))
      (node (ref "R24") (pin "2") (pinfunction "2_2") (pintype "passive"))
      (node (ref "U6") (pin "2") (pinfunction "2_2") (pintype "passive"))
    )
    (net (code "33") (name "/AD0") (class "Default")
      (node (ref "J2") (pin "1") (pinfunction "1_1") (pintype "passive"))
      (node (ref "U1") (pin "23") (pinfunction "PC0_(ADC0/PCINT8)_23") (pintype "passive"))
    )
    (net (code "34") (name "/AD1") (class "Default")
      (node (ref "J2") (pin "2") (pinfunction "2_2") (pintype "passive"))
      (node (ref "U1") (pin "24") (pinfunction "PC1_(ADC1/PCINT9)_24") (pintype "passive"))
    )
    (net (code "35") (name "/AD2") (class "Default")
      (node (ref "J2") (pin "3") (pinfunction "3_3") (pintype "passive"))
      (node (ref "U1") (pin "25") (pinfunction "PC2_(ADC2/PCINT10)_25") (pintype "passive"))
    )
    (net (code "36") (name "/AD3") (class "Default")
      (node (ref "J2") (pin "4") (pinfunction "4_4") (pintype "passive"))
      (node (ref "U1") (pin "26") (pinfunction "PC3_(ADC3/PCINT11)_26") (pintype "passive"))
    )
    (net (code "37") (name "/AD4{slash}SDA") (class "Default")
      (node (ref "J2") (pin "5") (pinfunction "5_5") (pintype "passive"))
      (node (ref "J4") (pin "9") (pinfunction "9_9") (pintype "passive"))
      (node (ref "U1") (pin "27") (pinfunction "PC4_(ADC4/SDA/PCINT12)_27") (pintype "passive"))
    )
    (net (code "38") (name "/AD5{slash}SCI") (class "Default")
      (node (ref "J2") (pin "6") (pinfunction "6_6") (pintype "passive"))
      (node (ref "J4") (pin "10") (pinfunction "10_10") (pintype "passive"))
      (node (ref "U1") (pin "28") (pinfunction "PC5_(ADC5/SCL/PCINT13)_28") (pintype "passive"))
    )
    (net (code "39") (name "/BUTTON_RESETn") (class "Default")
      (node (ref "D6") (pin "2") (pinfunction "Anode_2") (pintype "passive"))
      (node (ref "R20") (pin "1") (pinfunction "1_1") (pintype "passive"))
      (node (ref "R24") (pin "1") (pinfunction "1_1") (pintype "passive"))
      (node (ref "SW1") (pin "1") (pinfunction "1_1") (pintype "passive"))
      (node (ref "SW1") (pin "2") (pinfunction "2_2") (pintype "passive"))
    )
    (net (code "40") (name "/CON_USB_N") (class "Default")
      (node (ref "J7") (pin "2") (pinfunction "2_2") (pintype "passive"))
      (node (ref "R6") (pin "1") (pinfunction "1_1") (pintype "passive"))
      (node (ref "Z1") (pin "2") (pinfunction "2_2") (pintype "passive"))
    )
    (net (code "41") (name "/CON_USB_P") (class "Default")
      (node (ref "J7") (pin "3") (pinfunction "3_3") (pintype "passive"))
      (node (ref "R7") (pin "1") (pinfunction "1_1") (pintype "passive"))
      (node (ref "Z2") (pin "2") (pinfunction "2_2") (pintype "passive"))
    )
    (net (code "42") (name "/IO0") (class "Default")
      (node (ref "J3") (pin "1") (pinfunction "1_1") (pintype "passive"))
      (node (ref "R10") (pin "2") (pinfunction "2_2") (pintype "passive"))
      (node (ref "U1") (pin "2") (pinfunction "(PCINT16/RXD)_PD0_2") (pintype "passive"))
    )
    (net (code "43") (name "/IO1") (class "Default")
      (node (ref "J3") (pin "2") (pinfunction "2_2") (pintype "passive"))
      (node (ref "R11") (pin "2") (pinfunction "2_2") (pintype "passive"))
      (node (ref "U1") (pin "3") (pinfunction "(PCINT17/TXD)_PD1_3") (pintype "passive"))
    )
    (net (code "44") (name "/IO2") (class "Default")
      (node (ref "J3") (pin "3") (pinfunction "3_3") (pintype "passive"))
      (node (ref "U1") (pin "4") (pinfunction "(PCINT18/INT0)_PD2_4") (pintype "passive"))
    )
    (net (code "45") (name "/IO3") (class "Default")
      (node (ref "J3") (pin "4") (pinfunction "4_4") (pintype "passive"))
      (node (ref "U1") (pin "5") (pinfunction "(PCINT19/OC2B/INT1)_PD3_5") (pintype "passive"))
    )
    (net (code "46") (name "/IO4") (class "Default")
      (node (ref "J3") (pin "5") (pinfunction "5_5") (pintype "passive"))
      (node (ref "U1") (pin "6") (pinfunction "(PCINT20/XCK/T0)_PD4_6") (pintype "passive"))
    )
    (net (code "47") (name "/IO5") (class "Default")
      (node (ref "J3") (pin "6") (pinfunction "6_6") (pintype "passive"))
      (node (ref "U1") (pin "11") (pinfunction "(PCINT21/OC0B/T1)_PD5_11") (pintype "passive"))
    )
    (net (code "48") (name "/IO6") (class "Default")
      (node (ref "J3") (pin "7") (pinfunction "7_7") (pintype "passive"))
      (node (ref "U1") (pin "12") (pinfunction "(PCINT22/OC0A/AIN0)_PD6_12") (pintype "passive"))
    )
    (net (code "49") (name "/IO7") (class "Default")
      (node (ref "J3") (pin "8") (pinfunction "8_8") (pintype "passive"))
      (node (ref "U1") (pin "13") (pinfunction "(PCINT23/AIN1)_PD7_13") (pintype "passive"))
    )
    (net (code "50") (name "/IO8") (class "Default")
      (node (ref "J4") (pin "1") (pinfunction "1_1") (pintype "passive"))
      (node (ref "R22") (pin "1") (pinfunction "1_1") (pintype "passive"))
      (node (ref "U1") (pin "14") (pinfunction "(PCINT0/CLKO/ICP1)_PB0_14") (pintype "passive"))
    )
    (net (code "51") (name "/IO9") (class "Default")
      (node (ref "J4") (pin "2") (pinfunction "2_2") (pintype "passive"))
      (node (ref "U1") (pin "15") (pinfunction "PB1_(OC1A/PCINT1)_15") (pintype "passive"))
    )
    (net (code "52") (name "/MISO") (class "Default")
      (node (ref "J4") (pin "5") (pinfunction "5_5") (pintype "passive"))
      (node (ref "J5") (pin "1") (pinfunction "1_1") (pintype "passive"))
      (node (ref "U1") (pin "18") (pinfunction "PB4_(MISO/PCINT4)_18") (pintype "passive"))
    )
    (net (code "53") (name "/MOSI") (class "Default")
      (node (ref "J4") (pin "4") (pinfunction "4_4") (pintype "passive"))
      (node (ref "J5") (pin "4") (pinfunction "4_4") (pintype "passive"))
      (node (ref "U1") (pin "17") (pinfunction "PB3_(MOSI/OC2A/PCINT3)_17") (pintype "passive"))
    )
    (net (code "54") (name "/SCK") (class "Default")
      (node (ref "J4") (pin "6") (pinfunction "6_6") (pintype "passive"))
      (node (ref "J5") (pin "3") (pinfunction "3_3") (pintype "passive"))
      (node (ref "R13") (pin "2") (pinfunction "2_2") (pintype "passive"))
      (node (ref "U4") (pin "1") (pinfunction "1_1") (pintype "passive"))
      (node (ref "U4") (pin "2") (pinfunction "2_2") (pintype "passive"))
    )
    (net (code "55") (name "/SCK_R") (class "Default")
      (node (ref "R13") (pin "1") (pinfunction "1_1") (pintype "passive"))
      (node (ref "U1") (pin "19") (pinfunction "PB5_(SCK/PCINT5)_19") (pintype "passive"))
    )
    (net (code "56") (name "/SS") (class "Default")
      (node (ref "J4") (pin "3") (pinfunction "3_3") (pintype "passive"))
      (node (ref "U1") (pin "16") (pinfunction "PB2_(SS/OC1B/PCINT2)_16") (pintype "passive"))
    )
    (net (code "57") (name "/USB_N") (class "Default")
      (node (ref "R6") (pin "2") (pinfunction "2_2") (pintype "passive"))
      (node (ref "U2") (pin "30") (pinfunction "D-_30") (pintype "passive"))
    )
    (net (code "58") (name "/USB_P") (class "Default")
      (node (ref "R7") (pin "2") (pinfunction "2_2") (pintype "passive"))
      (node (ref "U2") (pin "29") (pinfunction "D+_29") (pintype "passive"))
    )
    (net (code "59") (name "/USER_BUTTON") (class "Default")
      (node (ref "R21") (pin "1") (pinfunction "1_1") (pintype "passive"))
      (node (ref "R25") (pin "1") (pinfunction "1_1") (pintype "passive"))
      (node (ref "SW2") (pin "1") (pinfunction "1_1") (pintype "passive"))
      (node (ref "SW2") (pin "2") (pinfunction "2_2") (pintype "passive"))
    )
    (net (code "60") (name "/USER_BUTTON_BUF") (class "Default")
      (node (ref "C33") (pin "1") (pinfunction "1_1") (pintype "passive"))
      (node (ref "R25") (pin "2") (pinfunction "2_2") (pintype "passive"))
      (node (ref "U7") (pin "1") (pinfunction "1_1") (pintype "passive"))
      (node (ref "U7") (pin "2") (pinfunction "2_2") (pintype "passive"))
    )
    (net (code "61") (name "GND") (class "Default")
      (node (ref "C1") (pin "2") (pinfunction "2_2") (pintype "passive"))
      (node (ref "C10") (pin "1") (pinfunction "1_1") (pintype "passive"))
      (node (ref "C12") (pin "2") (pinfunction "2_2") (pintype "passive"))
      (node (ref "C13") (pin "2") (pinfunction "2_2") (pintype "passive"))
      (node (ref "C14") (pin "2") (pinfunction "2_2") (pintype "passive"))
      (node (ref "C15") (pin "2") (pinfunction "2_2") (pintype "passive"))
      (node (ref "C16") (pin "2") (pinfunction "2_2") (pintype "passive"))
      (node (ref "C17") (pin "1") (pinfunction "1_1") (pintype "passive"))
      (node (ref "C19") (pin "2") (pinfunction "2_2") (pintype "passive"))
      (node (ref "C2") (pin "2") (pinfunction "2_2") (pintype "passive"))
      (node (ref "C20") (pin "1") (pinfunction "1_1") (pintype "passive"))
      (node (ref "C21") (pin "2") (pinfunction "2_2") (pintype "passive"))
      (node (ref "C22") (pin "1") (pinfunction "1_1") (pintype "passive"))
      (node (ref "C23") (pin "2") (pinfunction "2_2") (pintype "passive"))
      (node (ref "C24") (pin "2") (pinfunction "2_2") (pintype "passive"))
      (node (ref "C25") (pin "2") (pinfunction "2_2") (pintype "passive"))
      (node (ref "C26") (pin "2") (pinfunction "2_2") (pintype "passive"))
      (node (ref "C27") (pin "2") (pinfunction "2_2") (pintype "passive"))
      (node (ref "C28") (pin "2") (pinfunction "2_2") (pintype "passive"))
      (node (ref "C29") (pin "2") (pinfunction "2_2") (pintype "passive"))
      (node (ref "C3") (pin "2") (pinfunction "2_2") (pintype "passive"))
      (node (ref "C30") (pin "2") (pinfunction "2_2") (pintype "passive"))
      (node (ref "C31") (pin "2") (pinfunction "2_2") (pintype "passive"))
      (node (ref "C32") (pin "2") (pinfunction "2_2") (pintype "passive"))
      (node (ref "C33") (pin "2") (pinfunction "2_2") (pintype "passive"))
      (node (ref "C34") (pin "2") (pinfunction "2_2") (pintype "passive"))
      (node (ref "C4") (pin "2") (pinfunction "2_2") (pintype "passive"))
      (node (ref "C5") (pin "2") (pinfunction "2_2") (pintype "passive"))
      (node (ref "C6") (pin "2") (pinfunction "2_2") (pintype "passive"))
      (node (ref "C7") (pin "1") (pinfunction "1_1") (pintype "passive"))
      (node (ref "C8") (pin "1") (pinfunction "1_1") (pintype "passive"))
      (node (ref "C9") (pin "1") (pinfunction "1_1") (pintype "passive"))
      (node (ref "D1") (pin "1") (pinfunction "Cathode_1") (pintype "passive"))
      (node (ref "J1") (pin "6") (pinfunction "6_6") (pintype "passive"))
      (node (ref "J1") (pin "7") (pinfunction "7_7") (pintype "passive"))
      (node (ref "J4") (pin "7") (pinfunction "7_7") (pintype "passive"))
      (node (ref "J5") (pin "6") (pinfunction "6_6") (pintype "passive"))
      (node (ref "J6") (pin "6") (pinfunction "6_6") (pintype "passive"))
      (node (ref "J7") (pin "10") (pinfunction "10_10") (pintype "passive"))
      (node (ref "J7") (pin "11") (pinfunction "11_11") (pintype "passive"))
      (node (ref "J7") (pin "5") (pinfunction "5_5") (pintype "passive"))
      (node (ref "J7") (pin "6") (pinfunction "6_6") (pintype "passive"))
      (node (ref "J7") (pin "7") (pinfunction "7_7") (pintype "passive"))
      (node (ref "J7") (pin "8") (pinfunction "8_8") (pintype "passive"))
      (node (ref "J7") (pin "9") (pinfunction "9_9") (pintype "passive"))
      (node (ref "J9") (pin "1") (pinfunction "1_1") (pintype "passive"))
      (node (ref "MH1") (pin "1") (pinfunction "1_1") (pintype "passive"))
      (node (ref "MH2") (pin "1") (pinfunction "1_1") (pintype "passive"))
      (node (ref "MH3") (pin "1") (pinfunction "1_1") (pintype "passive"))
      (node (ref "R12") (pin "2") (pinfunction "2_2") (pintype "passive"))
      (node (ref "R8") (pin "2") (pinfunction "2_2") (pintype "passive"))
      (node (ref "SW1") (pin "3") (pinfunction "3_3") (pintype "passive"))
      (node (ref "SW1") (pin "4") (pinfunction "4_4") (pintype "passive"))
      (node (ref "SW2") (pin "3") (pinfunction "3_3") (pintype "passive"))
      (node (ref "SW2") (pin "4") (pinfunction "4_4") (pintype "passive"))
      (node (ref "U1") (pin "22") (pinfunction "GND_2_22") (pintype "passive"))
      (node (ref "U1") (pin "8") (pinfunction "GND_1_8") (pintype "passive"))
      (node (ref "U2") (pin "28") (pinfunction "UGND_28") (pintype "passive"))
      (node (ref "U2") (pin "3") (pinfunction "GND_3") (pintype "passive"))
      (node (ref "U3") (pin "3") (pinfunction "GND_3") (pintype "passive"))
      (node (ref "U3") (pin "6") (pinfunction "EPAD_6") (pintype "passive"))
      (node (ref "U4") (pin "3") (pinfunction "3_3") (pintype "passive"))
      (node (ref "U5") (pin "3") (pinfunction "3_3") (pintype "passive"))
      (node (ref "U6") (pin "3") (pinfunction "3_3") (pintype "passive"))
      (node (ref "U7") (pin "3") (pinfunction "3_3") (pintype "passive"))
      (node (ref "Z1") (pin "1") (pinfunction "1_1") (pintype "passive"))
      (node (ref "Z2") (pin "1") (pinfunction "1_1") (pintype "passive"))
    )
    (net (code "62") (name "Net-(C11-Pad2)") (class "Default")
      (node (ref "C11") (pin "2") (pinfunction "2_2") (pintype "passive"))
      (node (ref "JP1") (pin "1") (pinfunction "1_1") (pintype "passive"))
    )
    (net (code "63") (name "Net-(D1-Anode)") (class "Default")
      (node (ref "D1") (pin "2") (pinfunction "Anode_2") (pintype "passive"))
      (node (ref "R17") (pin "1") (pinfunction "1_1") (pintype "passive"))
    )
    (net (code "64") (name "Net-(D2-Anode)") (class "Default")
      (node (ref "D2") (pin "2") (pinfunction "Anode_2") (pintype "passive"))
      (node (ref "R15") (pin "1") (pinfunction "1_1") (pintype "passive"))
    )
    (net (code "65") (name "Net-(D2-Cathode)") (class "Default")
      (node (ref "D2") (pin "1") (pinfunction "Cathode_1") (pintype "passive"))
      (node (ref "U4") (pin "4") (pinfunction "4_4") (pintype "passive"))
    )
    (net (code "66") (name "Net-(D3-Anode)") (class "Default")
      (node (ref "D3") (pin "2") (pinfunction "Anode_2") (pintype "passive"))
      (node (ref "R2") (pin "1") (pinfunction "1_1") (pintype "passive"))
    )
    (net (code "67") (name "Net-(D4-Anode)") (class "Default")
      (node (ref "D4") (pin "2") (pinfunction "Anode_2") (pintype "passive"))
      (node (ref "R3") (pin "1") (pinfunction "1_1") (pintype "passive"))
    )
    (net (code "68") (name "Net-(D5-Anode)") (class "Default")
      (node (ref "D5") (pin "2") (pinfunction "Anode_2") (pintype "passive"))
      (node (ref "R19") (pin "1") (pinfunction "1_1") (pintype "passive"))
      (node (ref "R23") (pin "1") (pinfunction "1_1") (pintype "passive"))
    )
    (net (code "69") (name "Net-(J7-Pad4)") (class "Default")
      (node (ref "J7") (pin "4") (pinfunction "4_4") (pintype "passive"))
      (node (ref "R8") (pin "1") (pinfunction "1_1") (pintype "passive"))
    )
    (net (code "70") (name "Net-(JP1-Pad3)") (class "Default")
      (node (ref "JP1") (pin "3") (pinfunction "3_3") (pintype "passive"))
      (node (ref "R12") (pin "1") (pinfunction "1_1") (pintype "passive"))
    )
    (net (code "71") (name "Net-(R22-Pad2)") (class "Default")
      (node (ref "R22") (pin "2") (pinfunction "2_2") (pintype "passive"))
      (node (ref "U7") (pin "4") (pinfunction "4_4") (pintype "passive"))
    )
    (net (code "72") (name "unconnected-(J1-Pad1)") (class "Default")
      (node (ref "J1") (pin "1") (pinfunction "1_1") (pintype "passive+no_connect"))
    )
    (net (code "73") (name "unconnected-(J1-Pad8)") (class "Default")
      (node (ref "J1") (pin "8") (pinfunction "8_8") (pintype "passive+no_connect"))
    )
    (net (code "74") (name "unconnected-(MH4-Pad1)") (class "Default")
      (node (ref "MH4") (pin "1") (pinfunction "1_1") (pintype "passive+no_connect"))
    )
    (net (code "75") (name "unconnected-(U2-(AIN0_{slash}_INT1)_PD1-Pad7)") (class "Default")
      (node (ref "U2") (pin "7") (pinfunction "(AIN0_/_INT1)_PD1_7") (pintype "passive+no_connect"))
    )
    (net (code "76") (name "unconnected-(U2-(OC.0B_{slash}_INT0)_PD0-Pad6)") (class "Default")
      (node (ref "U2") (pin "6") (pinfunction "(OC.0B_/_INT0)_PD0_6") (pintype "passive+no_connect"))
    )
    (net (code "77") (name "unconnected-(U2-(PCINT11_{slash}AIN2_)_PC2-Pad5)") (class "Default")
      (node (ref "U2") (pin "5") (pinfunction "(PCINT11_/AIN2_)_PC2_5") (pintype "passive+no_connect"))
    )
    (net (code "78") (name "unconnected-(U2-(SS_{slash}_PCINT0)_PB0-Pad14)") (class "Default")
      (node (ref "U2") (pin "14") (pinfunction "(SS_/_PCINT0)_PB0_14") (pintype "passive+no_connect"))
    )
    (net (code "79") (name "unconnected-(U2-(~{RT}S_{slash}_AIN5_{slash}_INT6)_PD6-Pad12)") (class "Default")
      (node (ref "U2") (pin "12") (pinfunction "(~{RT}S_/_AIN5_/_INT6)_PD6_12") (pintype "passive+no_connect"))
    )
    (net (code "80") (name "unconnected-(U2-PC4_(PCINT10)-Pad26)") (class "Default")
      (node (ref "U2") (pin "26") (pinfunction "PC4_(PCINT10)_26") (pintype "passive+no_connect"))
    )
    (net (code "81") (name "unconnected-(U2-PC5_(_PCINT9{slash}_OC.1B)-Pad25)") (class "Default")
      (node (ref "U2") (pin "25") (pinfunction "PC5_(_PCINT9/_OC.1B)_25") (pintype "passive+no_connect"))
    )
    (net (code "82") (name "unconnected-(U2-PC6_(OC.1A_{slash}_PCINT8)-Pad23)") (class "Default")
      (node (ref "U2") (pin "23") (pinfunction "PC6_(OC.1A_/_PCINT8)_23") (pintype "passive+no_connect"))
    )
    (net (code "83") (name "unconnected-(U2-PC7_(INT4_{slash}_ICP1_{slash}_CLKO)-Pad22)") (class "Default")
      (node (ref "U2") (pin "22") (pinfunction "PC7_(INT4_/_ICP1_/_CLKO)_22") (pintype "passive+no_connect"))
    )
  )
)
